# Sheet2.net
KiCad netlist of a schematic drawn in Altium Designer
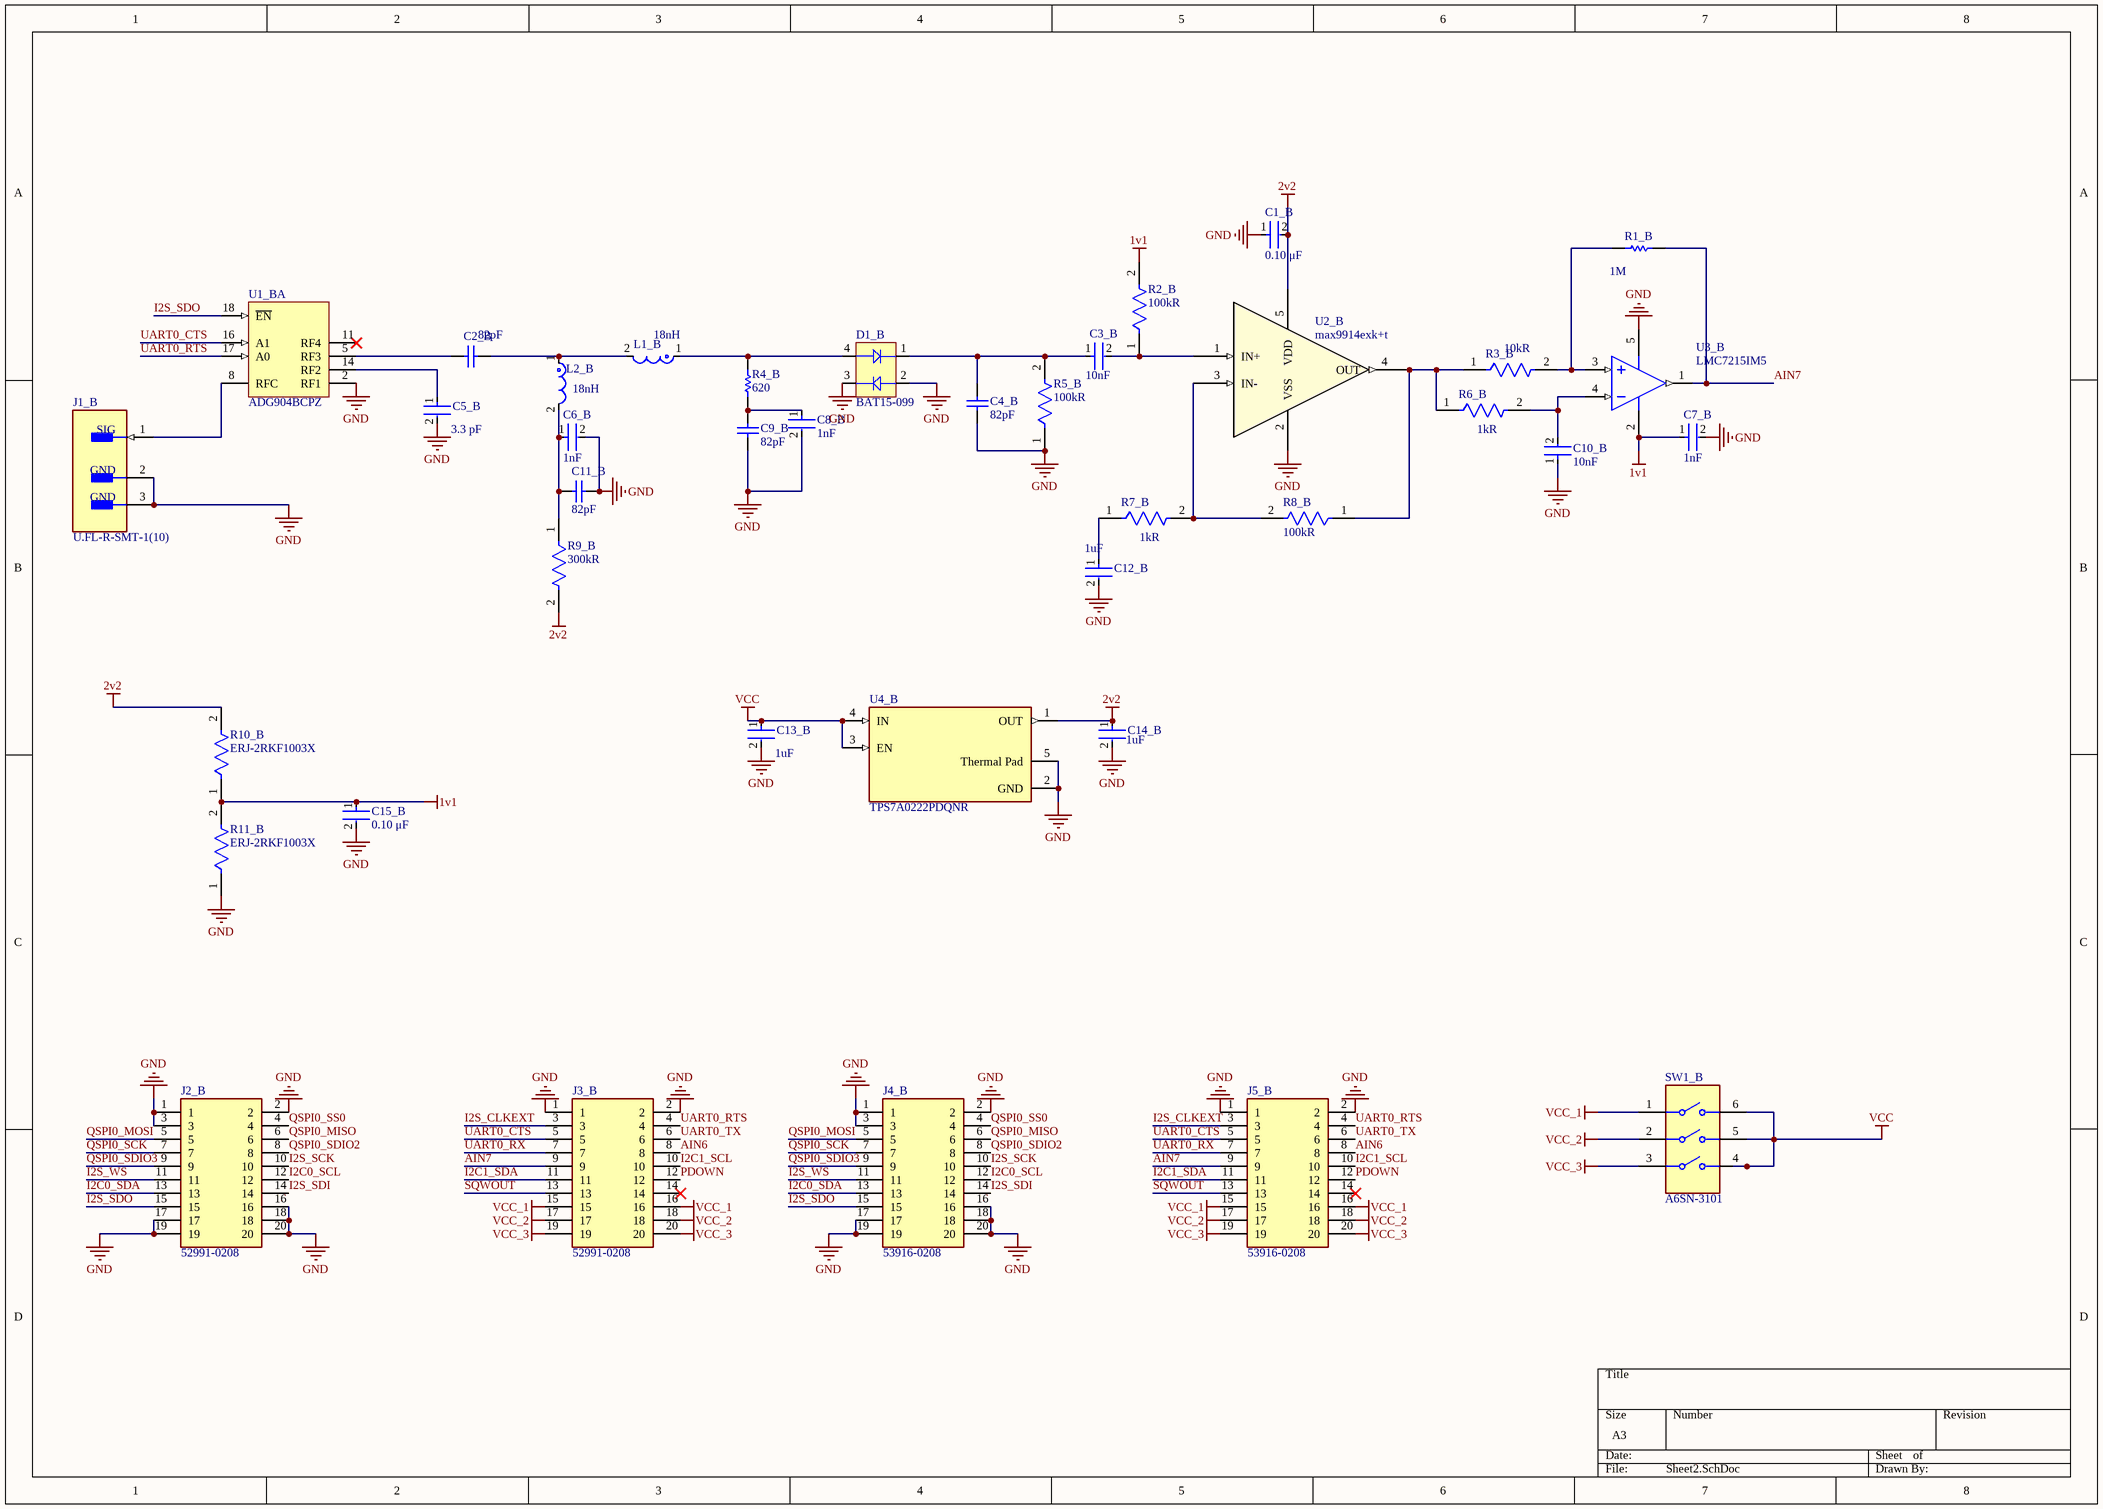
[diagram p0: Sheet2.SchDoc]

(export (version "E")
  (design (tool "Eeschema 10.0.6"))
  (components
    (comp (ref "C1_B")
      (value "C0402C104K8PACTU")
      (footprint "FP-C0402-BB-MFG")
      (description "CAP CER 0.1UF 10V X5R 0402")
      (fields
        (field (name "CAPACITANCE") "0.10 μF")
        (field (name "MANUFACTURER") "Kemet")
        (field (name "TOLERANCE") "0.1")
      )
      (libsource (lib "Altium Content Vault") (part "b4654b650e69147ec39a6b967a45e02"))
    )
    (comp (ref "C2_B")
      (value "82pF")
      (footprint "CAPC1005X55X25ML05T10")
      (fields (field (name "MANUFACTURER") "Murata") (field (name "PART NUMBER") "GRM1555C1H820JA01D"))
      (libsource (lib "Altium Content Vault") (part "CAP"))
    )
    (comp (ref "C3_B")
      (value "CL05B103KB5NNNC")
      (footprint "FP-CL165-IPC_C")
      (description "Cap Ceramic 10nF 50V X7R ±10% SMD 0402 +125°C Paper T/R")
      (fields
        (field (name "VOLTAGE") "50V")
        (field (name "TOLERANCE") "10%")
        (field (name "CAPACITANCE") "10nF")
      )
      (libsource (lib "Altium Content Vault") (part "b4654b650e69147ec39a6b967a45e02"))
    )
    (comp (ref "C4_B")
      (value "82pF")
      (footprint "CAPC1005X55X25ML05T10")
      (fields (field (name "MANUFACTURER") "Murata") (field (name "PART NUMBER") "GRM1555C1H820JA01D"))
      (libsource (lib "Altium Content Vault") (part "CAP"))
    )
    (comp (ref "C5_B")
      (value "C0402C339C5GACTU")
      (footprint "FP-C0402-BB-MFG")
      (description "Capacitor: ceramic; MLCC; 3.3pF; 50VDC; C0G; ±0.25pF; SMD; 0402")
      (fields
        (field (name "CAPACITANCE") "3.3 pF")
        (field (name "TOLERANCE") "0.25 pF")
        (field (name "MANUFACTURER") "Kemet")
      )
      (libsource (lib "Altium Content Vault") (part "b4654b650e69147ec39a6b967a45e02"))
    )
    (comp (ref "C6_B")
      (value "GRM1555C1H102JA01D")
      (footprint "FP-GRM155-0_05-IPC_B")
      (description "Chip Multilayer Ceramic Capacitors for General Purpose, 0402, 1000pF, C0G, 30ppm/°C, 5%, 50V")
      (fields
        (field (name "TOLERANCE") "5%")
        (field (name "VOLTAGE") "50V")
        (field (name "CAPACITANCE") "1nF")
      )
      (libsource (lib "Altium Content Vault") (part "02cd4be3c70576c341d710602a673aa"))
    )
    (comp (ref "C7_B")
      (value "GRM1555C1H102JA01D")
      (footprint "FP-GRM155-0_05-IPC_B")
      (description "Chip Multilayer Ceramic Capacitors for General Purpose, 0402, 1000pF, C0G, 30ppm/°C, 5%, 50V")
      (fields
        (field (name "TOLERANCE") "5%")
        (field (name "VOLTAGE") "50V")
        (field (name "CAPACITANCE") "1nF")
      )
      (libsource (lib "Altium Content Vault") (part "02cd4be3c70576c341d710602a673aa"))
    )
    (comp (ref "C8_B")
      (value "GRM1555C1H102JA01D")
      (footprint "FP-GRM155-0_05-IPC_B")
      (description "Chip Multilayer Ceramic Capacitors for General Purpose, 0402, 1000pF, C0G, 30ppm/°C, 5%, 50V")
      (fields
        (field (name "TOLERANCE") "5%")
        (field (name "VOLTAGE") "50V")
        (field (name "CAPACITANCE") "1nF")
      )
      (libsource (lib "Altium Content Vault") (part "02cd4be3c70576c341d710602a673aa"))
    )
    (comp (ref "C9_B")
      (value "82pF")
      (footprint "CAPC1005X55X25ML05T10")
      (fields (field (name "MANUFACTURER") "Murata") (field (name "PART NUMBER") "GRM1555C1H820JA01D"))
      (libsource (lib "Altium Content Vault") (part "CAP"))
    )
    (comp (ref "C10_B")
      (value "CL05B103KB5NNNC")
      (footprint "FP-CL165-IPC_C")
      (description "Cap Ceramic 10nF 50V X7R ±10% SMD 0402 +125°C Paper T/R")
      (fields
        (field (name "VOLTAGE") "50V")
        (field (name "TOLERANCE") "10%")
        (field (name "CAPACITANCE") "10nF")
      )
      (libsource (lib "Altium Content Vault") (part "b4654b650e69147ec39a6b967a45e02"))
    )
    (comp (ref "C11_B")
      (value "82pF")
      (footprint "CAPC1005X55X25ML05T10")
      (fields (field (name "MANUFACTURER") "Murata") (field (name "PART NUMBER") "GRM1555C1H820JA01D"))
      (libsource (lib "Altium Content Vault") (part "CAP"))
    )
    (comp (ref "C12_B")
      (value "C0402C105K8PACTU")
      (footprint "FP-C0402C105K8PACTU-MFG")
      (description "CAP CER 1UF 10V X5R 0402")
      (fields
        (field (name "CAPACITANCE") "1uF")
        (field (name "VOLTAGE") "10V")
        (field (name "TOLERANCE") "10%")
      )
      (libsource (lib "Altium Content Vault") (part "11868f565c42a9108669ba33697ecf6"))
    )
    (comp (ref "C13_B")
      (value "C0402C105K8PACTU")
      (footprint "FP-C0402C105K8PACTU-MFG")
      (description "CAP CER 1UF 10V X5R 0402")
      (fields
        (field (name "CAPACITANCE") "1uF")
        (field (name "VOLTAGE") "10V")
        (field (name "TOLERANCE") "10%")
      )
      (libsource (lib "Altium Content Vault") (part "11868f565c42a9108669ba33697ecf6"))
    )
    (comp (ref "C14_B")
      (value "C0402C105K8PACTU")
      (footprint "FP-C0402C105K8PACTU-MFG")
      (description "CAP CER 1UF 10V X5R 0402")
      (fields
        (field (name "CAPACITANCE") "1uF")
        (field (name "VOLTAGE") "10V")
        (field (name "TOLERANCE") "10%")
      )
      (libsource (lib "Altium Content Vault") (part "11868f565c42a9108669ba33697ecf6"))
    )
    (comp (ref "C15_B")
      (value "C0402C104K8PACTU")
      (footprint "FP-C0402-BB-MFG")
      (description "CAP CER 0.1UF 10V X5R 0402")
      (fields
        (field (name "CAPACITANCE") "0.10 μF")
        (field (name "MANUFACTURER") "Kemet")
        (field (name "TOLERANCE") "0.1")
      )
      (libsource (lib "Altium Content Vault") (part "b4654b650e69147ec39a6b967a45e02"))
    )
    (comp (ref "D1_B")
      (value "BAT15-099")
      (footprint "INF-SOT143-4-1_V")
      (description "Single Silicon Schottky Diode, 110 mA IF Max, SOT143-4-1, Green")
      (fields (field (name "MANUFACTURER") "Infineon"))
      (libsource (lib "Altium Content Vault") (part "INF-BAT15-099-4"))
    )
    (comp (ref "J1_B")
      (value "U.FL-R-SMT-1(10)")
      (footprint "FP-U_FL-R-SMT-1_10-MFG")
      (description "CONN U.FL RCPT STR 50 OHM SMD")
      (libsource (lib "Altium Content Vault") (part "7158abf7d987fa84906f6fb0d115710"))
    )
    (comp (ref "J2_B")
      (value "52991-0208")
      (footprint "MOLEX_52991-0208")
      (description "20 Position Connector Receptacle, Center Strip Contacts Surface Mount Gold")
      (fields (field (name "MF") "Molex"))
      (libsource (lib "52991-0208") (part "52991-0208"))
    )
    (comp (ref "J3_B")
      (value "52991-0208")
      (footprint "MOLEX_52991-0208")
      (description "20 Position Connector Receptacle, Center Strip Contacts Surface Mount Gold")
      (fields (field (name "MF") "Molex"))
      (libsource (lib "52991-0208") (part "52991-0208"))
    )
    (comp (ref "J4_B")
      (value "53916-0208")
      (footprint "MOLEX-  539160208")
      (libsource (lib "52991-0208") (part "53916-0208"))
    )
    (comp (ref "J5_B")
      (value "53916-0208")
      (footprint "MOLEX-  539160208")
      (libsource (lib "52991-0208") (part "53916-0208"))
    )
    (comp (ref "L1_B")
      (value "LQG15HN18NJ02D")
      (footprint "FP-LQG15HH_02-IPC_A")
      (description "Multilayer type RF Inductor 18nH ±5% 0.51Ω 350mA 0402")
      (fields (field (name "TOLERANCE") "5%") (field (name "INDUCTANCE") "18nH"))
      (libsource (lib "Altium Content Vault") (part "4cc4b267dca4c8e51f7102f422741d8"))
    )
    (comp (ref "L2_B")
      (value "LQG15HN18NJ02D")
      (footprint "FP-LQG15HH_02-IPC_A")
      (description "Multilayer type RF Inductor 18nH ±5% 0.51Ω 350mA 0402")
      (fields (field (name "TOLERANCE") "5%") (field (name "INDUCTANCE") "18nH"))
      (libsource (lib "Altium Content Vault") (part "4cc4b267dca4c8e51f7102f422741d8"))
    )
    (comp (ref "R1_B")
      (value "ERJ-3EKF1004V")
      (footprint "RESC1608X55X30LL15T15")
      (fields (field (name "MANUFACTURER") "Panasonic") (field (name "RESISTANCE") "1M"))
      (libsource (lib "Altium Content Vault") (part "RES"))
    )
    (comp (ref "R2_B")
      (value "ERJ-2RKF1003X")
      (footprint "FP-ERJ2RK-IPC_C")
      (description "RES SMD 100K OHM 1% 1/10W 0402")
      (fields (field (name "RESISTANCE") "100kR") (field (name "TOLERANCE") "1%"))
      (libsource (lib "Altium Content Vault") (part "1029c3af85768c4190bb7ad29bc67b5"))
    )
    (comp (ref "R3_B")
      (value "CRCW040210K0FKED")
      (footprint "FP-CRCW0402-e3-IPC_B")
      (description "RES SMD 10K OHM 1% 1/16W 0402")
      (fields (field (name "RESISTANCE") "10kR") (field (name "TOLERANCE") "1%"))
      (libsource (lib "Altium Content Vault") (part "1029c3af85768c4190bb7ad29bc67b5"))
    )
    (comp (ref "R4_B")
      (value "620")
      (footprint "RESC1005X40X25NL05T05")
      (fields (field (name "PART NUMBER") "ERJ-2RKF6200X") (field (name "MANUFACTURER") "Panasonic"))
      (libsource (lib "Altium Content Vault") (part "RES"))
    )
    (comp (ref "R5_B")
      (value "ERJ-2RKF1003X")
      (footprint "FP-ERJ2RK-IPC_C")
      (description "RES SMD 100K OHM 1% 1/10W 0402")
      (fields (field (name "RESISTANCE") "100kR") (field (name "TOLERANCE") "1%"))
      (libsource (lib "Altium Content Vault") (part "1029c3af85768c4190bb7ad29bc67b5"))
    )
    (comp (ref "R6_B")
      (value "CRCW04021K00FKED")
      (footprint "FP-CRCW0402-e3-MFG")
      (description "RES Thick Film, 1kΩ, 1%, 0.063W, 100ppm/°C, 0402")
      (fields (field (name "RESISTANCE") "1kR") (field (name "TOLERANCE") "1%"))
      (libsource (lib "Altium Content Vault") (part "1029c3af85768c4190bb7ad29bc67b5"))
    )
    (comp (ref "R7_B")
      (value "CRCW04021K00FKED")
      (footprint "FP-CRCW0402-e3-MFG")
      (description "RES Thick Film, 1kΩ, 1%, 0.063W, 100ppm/°C, 0402")
      (fields (field (name "RESISTANCE") "1kR") (field (name "TOLERANCE") "1%"))
      (libsource (lib "Altium Content Vault") (part "1029c3af85768c4190bb7ad29bc67b5"))
    )
    (comp (ref "R8_B")
      (value "ERJ-2RKF1003X")
      (footprint "FP-ERJ2RK-IPC_C")
      (description "RES SMD 100K OHM 1% 1/10W 0402")
      (fields (field (name "RESISTANCE") "100kR") (field (name "TOLERANCE") "1%"))
      (libsource (lib "Altium Content Vault") (part "1029c3af85768c4190bb7ad29bc67b5"))
    )
    (comp (ref "R9_B")
      (value "CRCW0402300KFKED")
      (footprint "FP-CRCW0402-e3-IPC_C")
      (description "RES Thick Film, 300kΩ, 1%, 0.063W, 100ppm/°C, 0402")
      (fields (field (name "RESISTANCE") "300kR") (field (name "TOLERANCE") "1%"))
      (libsource (lib "Altium Content Vault") (part "1029c3af85768c4190bb7ad29bc67b5"))
    )
    (comp (ref "R10_B")
      (value "ERJ-2RKF1003X")
      (footprint "FP-ERJ2RK-IPC_C")
      (description "RES SMD 100K OHM 1% 1/10W 0402")
      (fields (field (name "TOLERANCE") "1%"))
      (libsource (lib "Altium Content Vault") (part "1029c3af85768c4190bb7ad29bc67b5"))
    )
    (comp (ref "R11_B")
      (value "ERJ-2RKF1003X")
      (footprint "FP-ERJ2RK-IPC_C")
      (description "RES SMD 100K OHM 1% 1/10W 0402")
      (fields (field (name "TOLERANCE") "1%"))
      (libsource (lib "Altium Content Vault") (part "1029c3af85768c4190bb7ad29bc67b5"))
    )
    (comp (ref "SW1_B")
      (value "A6SN-3101")
      (footprint "FP-A6SN-3101-MFG")
      (description "DIP Switches / SIP Switches 3P Knife-Edge, 2.3mm Slide SMT Flat-Act")
      (fields (field (name "MANUFACTURER") "Omron Electronics Inc-EMC Div"))
      (libsource (lib "Altium Content Vault") (part "c5ed29025a0a80be921a75429a93ff4"))
    )
    (comp (ref "U1_B")
      (value "ADG904BCPZ")
      (footprint "ADI-CP-20-6_N")
      (fields (field (name "MANUFACTURER") "Analog Devices"))
      (libsource (lib "Altium Content Vault") (part "ADI-ADG904-CP-20-1"))
    )
    (comp (ref "U2_B")
      (value "max9914exk+t")
      (footprint "21-0076E_MXM")
      (description "No Description Available")
      (fields (field (name "COPYRIGHT") "Copyright (C) 2021 Accelerated Designs. All rights reserved"))
      (libsource (lib "max9914exk&plus_t") (part "max9914exk+t"))
    )
    (comp (ref "U3_B")
      (value "LMC7215IM5")
      (footprint "DBV0005A_N")
      (description "Micro-Power, Rail-to-Rail CMOS Comparators with Open-Drain/Push-Pull Outputs, 5-pin SOT-23")
      (fields (field (name "MANUFACTURER") "Texas Instruments"))
      (libsource (lib "Altium Content Vault") (part "AN-COMP-LMC7211-5"))
    )
    (comp (ref "U4_B")
      (value "TPS7A0222PDQNR")
      (footprint "FP-DQN0004A-MFG")
      (description "IC REG LINEAR 1.8V 200MA 4X2SON")
      (libsource (lib "Altium Content Vault") (part "6c364980ee72d5ff55aeee3d6240250"))
    )
  )
  (nets
    (net (code "1") (name "/AIN6") (class "Default")
      (node (ref "J3_B") (pin "8") (pinfunction "8_8") (pintype "passive"))
      (node (ref "J5_B") (pin "8") (pinfunction "8_8") (pintype "passive"))
    )
    (net (code "2") (name "/AIN7") (class "Default")
      (node (ref "J3_B") (pin "9") (pinfunction "9_9") (pintype "passive"))
      (node (ref "J5_B") (pin "9") (pinfunction "9_9") (pintype "passive"))
      (node (ref "R1_B") (pin "2") (pinfunction "2_2") (pintype "passive"))
      (node (ref "U3_B") (pin "1") (pinfunction "OUT_1") (pintype "output"))
    )
    (net (code "3") (name "/I2C0_SCL") (class "Default")
      (node (ref "J2_B") (pin "12") (pinfunction "12_12") (pintype "passive"))
      (node (ref "J4_B") (pin "12") (pinfunction "12_12") (pintype "passive"))
    )
    (net (code "4") (name "/I2C0_SDA") (class "Default")
      (node (ref "J2_B") (pin "13") (pinfunction "13_13") (pintype "passive"))
      (node (ref "J4_B") (pin "13") (pinfunction "13_13") (pintype "passive"))
    )
    (net (code "5") (name "/I2C1_SCL") (class "Default")
      (node (ref "J3_B") (pin "10") (pinfunction "10_10") (pintype "passive"))
      (node (ref "J5_B") (pin "10") (pinfunction "10_10") (pintype "passive"))
    )
    (net (code "6") (name "/I2C1_SDA") (class "Default")
      (node (ref "J3_B") (pin "11") (pinfunction "11_11") (pintype "passive"))
      (node (ref "J5_B") (pin "11") (pinfunction "11_11") (pintype "passive"))
    )
    (net (code "7") (name "/I2S_CLKEXT") (class "Default")
      (node (ref "J3_B") (pin "3") (pinfunction "3_3") (pintype "passive"))
      (node (ref "J5_B") (pin "3") (pinfunction "3_3") (pintype "passive"))
    )
    (net (code "8") (name "/I2S_SCK") (class "Default")
      (node (ref "J2_B") (pin "10") (pinfunction "10_10") (pintype "passive"))
      (node (ref "J4_B") (pin "10") (pinfunction "10_10") (pintype "passive"))
    )
    (net (code "9") (name "/I2S_SDI") (class "Default")
      (node (ref "J2_B") (pin "14") (pinfunction "14_14") (pintype "passive"))
      (node (ref "J4_B") (pin "14") (pinfunction "14_14") (pintype "passive"))
    )
    (net (code "10") (name "/I2S_SDO") (class "Default")
      (node (ref "J2_B") (pin "15") (pinfunction "15_15") (pintype "passive"))
      (node (ref "J4_B") (pin "15") (pinfunction "15_15") (pintype "passive"))
      (node (ref "U1_B") (pin "18") (pinfunction "~{EN}_18") (pintype "input"))
    )
    (net (code "11") (name "/I2S_WS") (class "Default")
      (node (ref "J2_B") (pin "11") (pinfunction "11_11") (pintype "passive"))
      (node (ref "J4_B") (pin "11") (pinfunction "11_11") (pintype "passive"))
    )
    (net (code "12") (name "/PDOWN") (class "Default")
      (node (ref "J3_B") (pin "12") (pinfunction "12_12") (pintype "passive"))
      (node (ref "J5_B") (pin "12") (pinfunction "12_12") (pintype "passive"))
    )
    (net (code "13") (name "/QSPI0_MISO") (class "Default")
      (node (ref "J2_B") (pin "6") (pinfunction "6_6") (pintype "passive"))
      (node (ref "J4_B") (pin "6") (pinfunction "6_6") (pintype "passive"))
    )
    (net (code "14") (name "/QSPI0_MOSI") (class "Default")
      (node (ref "J2_B") (pin "5") (pinfunction "5_5") (pintype "passive"))
      (node (ref "J4_B") (pin "5") (pinfunction "5_5") (pintype "passive"))
    )
    (net (code "15") (name "/QSPI0_SCK") (class "Default")
      (node (ref "J2_B") (pin "7") (pinfunction "7_7") (pintype "passive"))
      (node (ref "J4_B") (pin "7") (pinfunction "7_7") (pintype "passive"))
    )
    (net (code "16") (name "/QSPI0_SDIO2") (class "Default")
      (node (ref "J2_B") (pin "8") (pinfunction "8_8") (pintype "passive"))
      (node (ref "J4_B") (pin "8") (pinfunction "8_8") (pintype "passive"))
    )
    (net (code "17") (name "/QSPI0_SDIO3") (class "Default")
      (node (ref "J2_B") (pin "9") (pinfunction "9_9") (pintype "passive"))
      (node (ref "J4_B") (pin "9") (pinfunction "9_9") (pintype "passive"))
    )
    (net (code "18") (name "/QSPI0_SS0") (class "Default")
      (node (ref "J2_B") (pin "4") (pinfunction "4_4") (pintype "passive"))
      (node (ref "J4_B") (pin "4") (pinfunction "4_4") (pintype "passive"))
    )
    (net (code "19") (name "/SQWOUT") (class "Default")
      (node (ref "J3_B") (pin "13") (pinfunction "13_13") (pintype "passive"))
      (node (ref "J5_B") (pin "13") (pinfunction "13_13") (pintype "passive"))
    )
    (net (code "20") (name "/UART0_CTS") (class "Default")
      (node (ref "J3_B") (pin "5") (pinfunction "5_5") (pintype "passive"))
      (node (ref "J5_B") (pin "5") (pinfunction "5_5") (pintype "passive"))
      (node (ref "U1_B") (pin "16") (pinfunction "A1_16") (pintype "input"))
    )
    (net (code "21") (name "/UART0_RTS") (class "Default")
      (node (ref "J3_B") (pin "4") (pinfunction "4_4") (pintype "passive"))
      (node (ref "J5_B") (pin "4") (pinfunction "4_4") (pintype "passive"))
      (node (ref "U1_B") (pin "17") (pinfunction "A0_17") (pintype "input"))
    )
    (net (code "22") (name "/UART0_RX") (class "Default")
      (node (ref "J3_B") (pin "7") (pinfunction "7_7") (pintype "passive"))
      (node (ref "J5_B") (pin "7") (pinfunction "7_7") (pintype "passive"))
    )
    (net (code "23") (name "/UART0_TX") (class "Default")
      (node (ref "J3_B") (pin "6") (pinfunction "6_6") (pintype "passive"))
      (node (ref "J5_B") (pin "6") (pinfunction "6_6") (pintype "passive"))
    )
    (net (code "24") (name "1v1") (class "Default")
      (node (ref "C15_B") (pin "1") (pinfunction "1_1") (pintype "passive"))
      (node (ref "C7_B") (pin "1") (pinfunction "1_1") (pintype "passive"))
      (node (ref "R10_B") (pin "1") (pinfunction "1_1") (pintype "passive"))
      (node (ref "R11_B") (pin "2") (pinfunction "2_2") (pintype "passive"))
      (node (ref "R2_B") (pin "2") (pinfunction "2_2") (pintype "passive"))
      (node (ref "U3_B") (pin "2") (pinfunction "V+_2") (pintype "power_in"))
    )
    (net (code "25") (name "2v2") (class "Default")
      (node (ref "C14_B") (pin "1") (pinfunction "1_1") (pintype "passive"))
      (node (ref "C1_B") (pin "2") (pinfunction "2_2") (pintype "passive"))
      (node (ref "R10_B") (pin "2") (pinfunction "2_2") (pintype "passive"))
      (node (ref "R9_B") (pin "2") (pinfunction "2_2") (pintype "passive"))
      (node (ref "U2_B") (pin "5") (pinfunction "VDD_5") (pintype "power_in"))
      (node (ref "U4_B") (pin "1") (pinfunction "OUT_1") (pintype "output"))
    )
    (net (code "26") (name "GND") (class "Default")
      (node (ref "C10_B") (pin "1") (pinfunction "1_1") (pintype "passive"))
      (node (ref "C11_B") (pin "2") (pinfunction "2_2") (pintype "passive"))
      (node (ref "C12_B") (pin "2") (pinfunction "2_2") (pintype "passive"))
      (node (ref "C13_B") (pin "2") (pinfunction "2_2") (pintype "passive"))
      (node (ref "C14_B") (pin "2") (pinfunction "2_2") (pintype "passive"))
      (node (ref "C15_B") (pin "2") (pinfunction "2_2") (pintype "passive"))
      (node (ref "C1_B") (pin "1") (pinfunction "1_1") (pintype "passive"))
      (node (ref "C4_B") (pin "1") (pinfunction "1_1") (pintype "passive"))
      (node (ref "C5_B") (pin "2") (pinfunction "2_2") (pintype "passive"))
      (node (ref "C6_B") (pin "2") (pinfunction "2_2") (pintype "passive"))
      (node (ref "C7_B") (pin "2") (pinfunction "2_2") (pintype "passive"))
      (node (ref "C8_B") (pin "2") (pinfunction "2_2") (pintype "passive"))
      (node (ref "C9_B") (pin "1") (pinfunction "1_1") (pintype "passive"))
      (node (ref "D1_B") (pin "2") (pinfunction "A2_2") (pintype "passive"))
      (node (ref "D1_B") (pin "3") (pinfunction "K2_3") (pintype "passive"))
      (node (ref "J1_B") (pin "2") (pinfunction "GND_2") (pintype "power_in"))
      (node (ref "J1_B") (pin "3") (pinfunction "GND_3") (pintype "power_in"))
      (node (ref "J2_B") (pin "1") (pinfunction "1_1") (pintype "passive"))
      (node (ref "J2_B") (pin "16") (pinfunction "16_16") (pintype "passive"))
      (node (ref "J2_B") (pin "17") (pinfunction "17_17") (pintype "passive"))
      (node (ref "J2_B") (pin "18") (pinfunction "18_18") (pintype "passive"))
      (node (ref "J2_B") (pin "19") (pinfunction "19_19") (pintype "passive"))
      (node (ref "J2_B") (pin "2") (pinfunction "2_2") (pintype "passive"))
      (node (ref "J2_B") (pin "20") (pinfunction "20_20") (pintype "passive"))
      (node (ref "J2_B") (pin "3") (pinfunction "3_3") (pintype "passive"))
      (node (ref "J3_B") (pin "1") (pinfunction "1_1") (pintype "passive"))
      (node (ref "J3_B") (pin "2") (pinfunction "2_2") (pintype "passive"))
      (node (ref "J4_B") (pin "1") (pinfunction "1_1") (pintype "passive"))
      (node (ref "J4_B") (pin "16") (pinfunction "16_16") (pintype "passive"))
      (node (ref "J4_B") (pin "17") (pinfunction "17_17") (pintype "passive"))
      (node (ref "J4_B") (pin "18") (pinfunction "18_18") (pintype "passive"))
      (node (ref "J4_B") (pin "19") (pinfunction "19_19") (pintype "passive"))
      (node (ref "J4_B") (pin "2") (pinfunction "2_2") (pintype "passive"))
      (node (ref "J4_B") (pin "20") (pinfunction "20_20") (pintype "passive"))
      (node (ref "J4_B") (pin "3") (pinfunction "3_3") (pintype "passive"))
      (node (ref "J5_B") (pin "1") (pinfunction "1_1") (pintype "passive"))
      (node (ref "J5_B") (pin "2") (pinfunction "2_2") (pintype "passive"))
      (node (ref "R11_B") (pin "1") (pinfunction "1_1") (pintype "passive"))
      (node (ref "R5_B") (pin "1") (pinfunction "1_1") (pintype "passive"))
      (node (ref "U1_B") (pin "2") (pinfunction "RF1_2") (pintype "passive"))
      (node (ref "U2_B") (pin "2") (pinfunction "VSS_2") (pintype "power_in"))
      (node (ref "U3_B") (pin "5") (pinfunction "V-_5") (pintype "power_in"))
      (node (ref "U4_B") (pin "2") (pinfunction "GND_2") (pintype "power_in"))
      (node (ref "U4_B") (pin "5") (pinfunction "Thermal_Pad_5") (pintype "power_in"))
    )
    (net (code "27") (name "Net-(C2_B-Pad2)") (class "Default")
      (node (ref "C2_B") (pin "2") (pinfunction "2_2") (pintype "passive"))
      (node (ref "L1_B") (pin "2") (pinfunction "2_2") (pintype "passive"))
      (node (ref "L2_B") (pin "1") (pinfunction "1_1") (pintype "passive"))
    )
    (net (code "28") (name "Net-(C8_B-Pad1)") (class "Default")
      (node (ref "C8_B") (pin "1") (pinfunction "1_1") (pintype "passive"))
      (node (ref "C9_B") (pin "2") (pinfunction "2_2") (pintype "passive"))
      (node (ref "R4_B") (pin "1") (pinfunction "1_1") (pintype "passive"))
    )
    (net (code "29") (name "Net-(C11_B-Pad1)") (class "Default")
      (node (ref "C11_B") (pin "1") (pinfunction "1_1") (pintype "passive"))
      (node (ref "C6_B") (pin "1") (pinfunction "1_1") (pintype "passive"))
      (node (ref "L2_B") (pin "2") (pinfunction "2_2") (pintype "passive"))
      (node (ref "R9_B") (pin "1") (pinfunction "1_1") (pintype "passive"))
    )
    (net (code "30") (name "Net-(C12_B-Pad1)") (class "Default")
      (node (ref "C12_B") (pin "1") (pinfunction "1_1") (pintype "passive"))
      (node (ref "R7_B") (pin "1") (pinfunction "1_1") (pintype "passive"))
    )
    (net (code "31") (name "Net-(D1_B-A1)") (class "Default")
      (node (ref "D1_B") (pin "4") (pinfunction "A1_4") (pintype "passive"))
      (node (ref "L1_B") (pin "1") (pinfunction "1_1") (pintype "passive"))
      (node (ref "R4_B") (pin "2") (pinfunction "2_2") (pintype "passive"))
    )
    (net (code "32") (name "Net-(D1_B-K1)") (class "Default")
      (node (ref "C3_B") (pin "1") (pinfunction "1_1") (pintype "passive"))
      (node (ref "C4_B") (pin "2") (pinfunction "2_2") (pintype "passive"))
      (node (ref "D1_B") (pin "1") (pinfunction "K1_1") (pintype "passive"))
      (node (ref "R5_B") (pin "2") (pinfunction "2_2") (pintype "passive"))
    )
    (net (code "33") (name "Net-(J1_B-SIG)") (class "Default")
      (node (ref "J1_B") (pin "1") (pinfunction "SIG_1") (pintype "input"))
      (node (ref "U1_B") (pin "8") (pinfunction "RFC_8") (pintype "passive"))
    )
    (net (code "34") (name "Net-(U1_BA-RF2)") (class "Default")
      (node (ref "C5_B") (pin "1") (pinfunction "1_1") (pintype "passive"))
      (node (ref "U1_B") (pin "14") (pinfunction "RF2_14") (pintype "passive"))
    )
    (net (code "35") (name "Net-(U1_BA-RF3)") (class "Default")
      (node (ref "C2_B") (pin "1") (pinfunction "1_1") (pintype "passive"))
      (node (ref "U1_B") (pin "5") (pinfunction "RF3_5") (pintype "passive"))
    )
    (net (code "36") (name "Net-(U2_B-IN+)") (class "Default")
      (node (ref "C3_B") (pin "2") (pinfunction "2_2") (pintype "passive"))
      (node (ref "R2_B") (pin "1") (pinfunction "1_1") (pintype "passive"))
      (node (ref "U2_B") (pin "1") (pinfunction "IN+_1") (pintype "input"))
    )
    (net (code "37") (name "Net-(U2_B-IN-)") (class "Default")
      (node (ref "R7_B") (pin "2") (pinfunction "2_2") (pintype "passive"))
      (node (ref "R8_B") (pin "2") (pinfunction "2_2") (pintype "passive"))
      (node (ref "U2_B") (pin "3") (pinfunction "IN-_3") (pintype "input"))
    )
    (net (code "38") (name "Net-(U2_B-OUT)") (class "Default")
      (node (ref "R3_B") (pin "1") (pinfunction "1_1") (pintype "passive"))
      (node (ref "R6_B") (pin "1") (pinfunction "1_1") (pintype "passive"))
      (node (ref "R8_B") (pin "1") (pinfunction "1_1") (pintype "passive"))
      (node (ref "U2_B") (pin "4") (pinfunction "OUT_4") (pintype "output"))
    )
    (net (code "39") (name "Net-(U3_B-IN+)") (class "Default")
      (node (ref "R1_B") (pin "1") (pinfunction "1_1") (pintype "passive"))
      (node (ref "R3_B") (pin "2") (pinfunction "2_2") (pintype "passive"))
      (node (ref "U3_B") (pin "3") (pinfunction "IN+_3") (pintype "input"))
    )
    (net (code "40") (name "Net-(U3_B-IN-)") (class "Default")
      (node (ref "C10_B") (pin "2") (pinfunction "2_2") (pintype "passive"))
      (node (ref "R6_B") (pin "2") (pinfunction "2_2") (pintype "passive"))
      (node (ref "U3_B") (pin "4") (pinfunction "IN-_4") (pintype "input"))
    )
    (net (code "41") (name "VCC") (class "Default")
      (node (ref "C13_B") (pin "1") (pinfunction "1_1") (pintype "passive"))
      (node (ref "SW1_B") (pin "4") (pinfunction "4_4") (pintype "passive"))
      (node (ref "SW1_B") (pin "5") (pinfunction "5_5") (pintype "passive"))
      (node (ref "SW1_B") (pin "6") (pinfunction "6_6") (pintype "passive"))
      (node (ref "U4_B") (pin "3") (pinfunction "EN_3") (pintype "input"))
      (node (ref "U4_B") (pin "4") (pinfunction "IN_4") (pintype "input"))
    )
    (net (code "42") (name "VCC_1") (class "Default")
      (node (ref "J3_B") (pin "15") (pinfunction "15_15") (pintype "passive"))
      (node (ref "J3_B") (pin "16") (pinfunction "16_16") (pintype "passive"))
      (node (ref "J5_B") (pin "15") (pinfunction "15_15") (pintype "passive"))
      (node (ref "J5_B") (pin "16") (pinfunction "16_16") (pintype "passive"))
      (node (ref "SW1_B") (pin "1") (pinfunction "1_1") (pintype "passive"))
    )
    (net (code "43") (name "VCC_2") (class "Default")
      (node (ref "J3_B") (pin "17") (pinfunction "17_17") (pintype "passive"))
      (node (ref "J3_B") (pin "18") (pinfunction "18_18") (pintype "passive"))
      (node (ref "J5_B") (pin "17") (pinfunction "17_17") (pintype "passive"))
      (node (ref "J5_B") (pin "18") (pinfunction "18_18") (pintype "passive"))
      (node (ref "SW1_B") (pin "2") (pinfunction "2_2") (pintype "passive"))
    )
    (net (code "44") (name "VCC_3") (class "Default")
      (node (ref "J3_B") (pin "19") (pinfunction "19_19") (pintype "passive"))
      (node (ref "J3_B") (pin "20") (pinfunction "20_20") (pintype "passive"))
      (node (ref "J5_B") (pin "19") (pinfunction "19_19") (pintype "passive"))
      (node (ref "J5_B") (pin "20") (pinfunction "20_20") (pintype "passive"))
      (node (ref "SW1_B") (pin "3") (pinfunction "3_3") (pintype "passive"))
    )
    (net (code "45") (name "unconnected-(J3_B-Pad14)") (class "Default")
      (node (ref "J3_B") (pin "14") (pinfunction "14_14") (pintype "passive+no_connect"))
    )
    (net (code "46") (name "unconnected-(J5_B-Pad14)") (class "Default")
      (node (ref "J5_B") (pin "14") (pinfunction "14_14") (pintype "passive+no_connect"))
    )
    (net (code "47") (name "unconnected-(U1_BA-RF4-Pad11)") (class "Default")
      (node (ref "U1_B") (pin "11") (pinfunction "RF4_11") (pintype "passive+no_connect"))
    )
  )
)
